# main.net
KiCad netlist of a schematic drawn in EAGLE
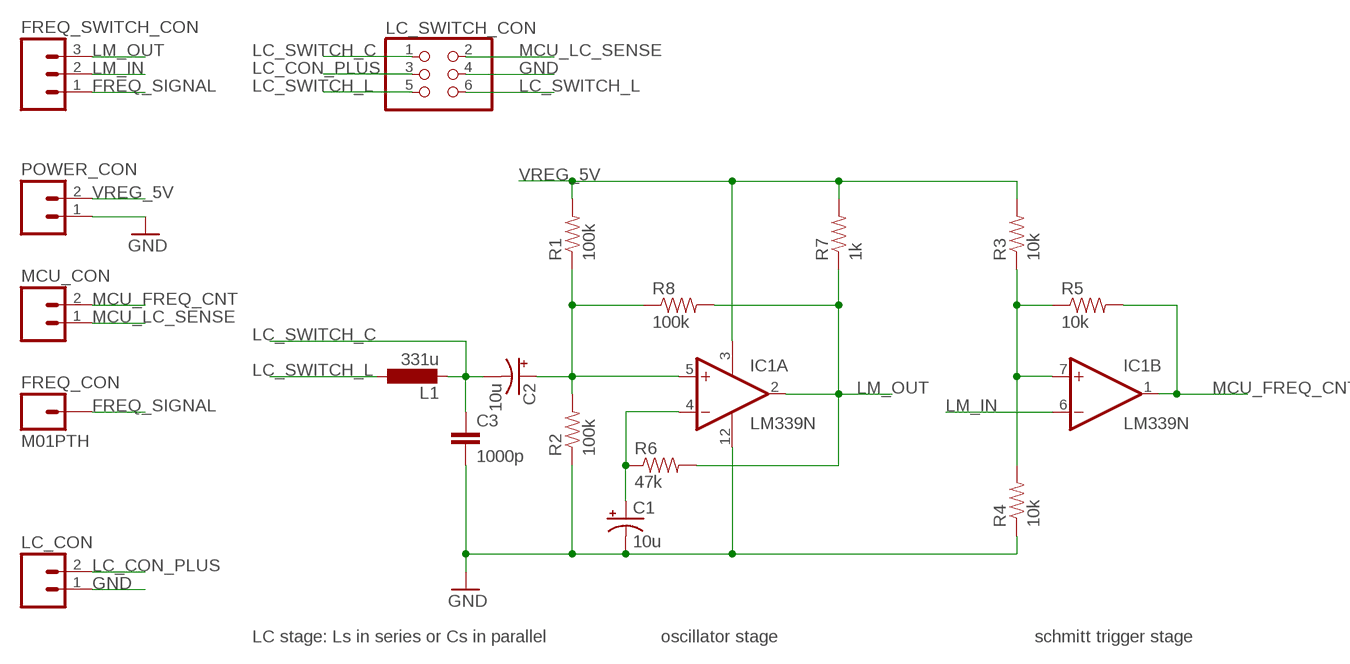
[diagram p0: schematic, sheet 1]

(export (version "E")
  (design (tool "Eeschema 10.0.6"))
  (components
    (comp (ref "C1")
      (value "10u")
      (footprint "eagle-import:CPOL-RADIAL-100UF-25V")
      (libsource (lib "eagle-import") (part "CAP_POLPTH1"))
    )
    (comp (ref "C2")
      (value "10u")
      (footprint "eagle-import:CPOL-RADIAL-100UF-25V")
      (libsource (lib "eagle-import") (part "CAP_POLPTH1"))
    )
    (comp (ref "C3")
      (value "1000p")
      (footprint "eagle-import:CAP-PTH-SMALL-KIT")
      (libsource (lib "eagle-import") (part "CAPKIT"))
    )
    (comp (ref "FREQ_CON")
      (value "M01PTH")
      (footprint "eagle-import:1X01")
      (libsource (lib "eagle-import") (part "M01PTH"))
    )
    (comp (ref "FREQ_SWITCH_CON")
      (value "M03PTH")
      (footprint "eagle-import:1X03")
      (libsource (lib "eagle-import") (part "M03PTH"))
    )
    (comp (ref "IC1")
      (value "LM339N")
      (footprint "eagle-import:DIL14")
      (libsource (lib "eagle-import") (part "LM339N"))
    )
    (comp (ref "L1")
      (value "331u")
      (footprint "eagle-import:0207_10")
      (libsource (lib "eagle-import") (part "L-EU0207/10"))
    )
    (comp (ref "LC_CON")
      (value "M02PTH")
      (footprint "eagle-import:1X02")
      (libsource (lib "eagle-import") (part "M02PTH"))
    )
    (comp (ref "LC_SWITCH_CON")
      (value "PINHD-2X3")
      (footprint "eagle-import:2X03")
      (libsource (lib "eagle-import") (part "PINHD-2X3"))
    )
    (comp (ref "MCU_CON")
      (value "M02PTH")
      (footprint "eagle-import:1X02")
      (libsource (lib "eagle-import") (part "M02PTH"))
    )
    (comp (ref "POWER_CON")
      (value "M02PTH")
      (footprint "eagle-import:1X02")
      (libsource (lib "eagle-import") (part "M02PTH"))
    )
    (comp (ref "R1")
      (value "100k")
      (footprint "eagle-import:AXIAL-0.4")
      (libsource (lib "eagle-import") (part "RESISTORPTH-1/4W"))
    )
    (comp (ref "R2")
      (value "100k")
      (footprint "eagle-import:AXIAL-0.4")
      (libsource (lib "eagle-import") (part "RESISTORPTH-1/4W"))
    )
    (comp (ref "R3")
      (value "10k")
      (footprint "eagle-import:AXIAL-0.4")
      (libsource (lib "eagle-import") (part "RESISTORPTH-1/4W"))
    )
    (comp (ref "R4")
      (value "10k")
      (footprint "eagle-import:AXIAL-0.4")
      (libsource (lib "eagle-import") (part "RESISTORPTH-1/4W"))
    )
    (comp (ref "R5")
      (value "10k")
      (footprint "eagle-import:AXIAL-0.4")
      (libsource (lib "eagle-import") (part "RESISTORPTH-1/4W"))
    )
    (comp (ref "R6")
      (value "47k")
      (footprint "eagle-import:AXIAL-0.4")
      (libsource (lib "eagle-import") (part "RESISTORPTH-1/4W"))
    )
    (comp (ref "R7")
      (value "1k")
      (footprint "eagle-import:AXIAL-0.4")
      (libsource (lib "eagle-import") (part "RESISTORPTH-1/4W"))
    )
    (comp (ref "R8")
      (value "100k")
      (footprint "eagle-import:AXIAL-0.4")
      (libsource (lib "eagle-import") (part "RESISTORPTH-1/4W"))
    )
  )
  (nets
    (net (code "1") (name "/FREQ_SIGNAL") (class "Default")
      (node (ref "FREQ_CON") (pin "1") (pinfunction "1_1") (pintype "passive"))
      (node (ref "FREQ_SWITCH_CON") (pin "1") (pinfunction "1_1") (pintype "passive"))
    )
    (net (code "2") (name "/LC_CON_PLUS") (class "Default")
      (node (ref "LC_CON") (pin "2") (pinfunction "2_2") (pintype "passive"))
      (node (ref "LC_SWITCH_CON") (pin "3") (pinfunction "3_3") (pintype "passive"))
    )
    (net (code "3") (name "/LC_SWITCH_C") (class "Default")
      (node (ref "C2") (pin "2") (pinfunction "-_2") (pintype "passive"))
      (node (ref "C3") (pin "1") (pinfunction "1_1") (pintype "passive"))
      (node (ref "L1") (pin "2") (pinfunction "2_2") (pintype "passive"))
      (node (ref "LC_SWITCH_CON") (pin "1") (pinfunction "1_1") (pintype "passive"))
    )
    (net (code "4") (name "/LC_SWITCH_L") (class "Default")
      (node (ref "L1") (pin "1") (pinfunction "1_1") (pintype "passive"))
      (node (ref "LC_SWITCH_CON") (pin "5") (pinfunction "5_5") (pintype "passive"))
      (node (ref "LC_SWITCH_CON") (pin "6") (pinfunction "6_6") (pintype "passive"))
    )
    (net (code "5") (name "/LM_IN") (class "Default")
      (node (ref "FREQ_SWITCH_CON") (pin "2") (pinfunction "2_2") (pintype "passive"))
      (node (ref "IC1") (pin "6") (pinfunction "-IN_6") (pintype "input"))
    )
    (net (code "6") (name "/LM_OUT") (class "Default")
      (node (ref "FREQ_SWITCH_CON") (pin "3") (pinfunction "3_3") (pintype "passive"))
      (node (ref "IC1") (pin "2") (pinfunction "OUT_2") (pintype "open_collector"))
      (node (ref "R6") (pin "P$2") (pinfunction "2_P$2") (pintype "passive"))
      (node (ref "R7") (pin "P$1") (pinfunction "1_P$1") (pintype "passive"))
      (node (ref "R8") (pin "P$2") (pinfunction "2_P$2") (pintype "passive"))
    )
    (net (code "7") (name "/MCU_FREQ_CNT") (class "Default")
      (node (ref "IC1") (pin "1") (pinfunction "OUT_1") (pintype "open_collector"))
      (node (ref "MCU_CON") (pin "2") (pinfunction "2_2") (pintype "passive"))
      (node (ref "R5") (pin "P$2") (pinfunction "2_P$2") (pintype "passive"))
    )
    (net (code "8") (name "/MCU_LC_SENSE") (class "Default")
      (node (ref "LC_SWITCH_CON") (pin "2") (pinfunction "2_2") (pintype "passive"))
      (node (ref "MCU_CON") (pin "1") (pinfunction "1_1") (pintype "passive"))
    )
    (net (code "9") (name "/VREG_5V") (class "Default")
      (node (ref "IC1") (pin "3") (pinfunction "V+_3") (pintype "power_in"))
      (node (ref "POWER_CON") (pin "2") (pinfunction "2_2") (pintype "passive"))
      (node (ref "R1") (pin "P$2") (pinfunction "2_P$2") (pintype "passive"))
      (node (ref "R3") (pin "P$2") (pinfunction "2_P$2") (pintype "passive"))
      (node (ref "R7") (pin "P$2") (pinfunction "2_P$2") (pintype "passive"))
    )
    (net (code "10") (name "GND") (class "Default")
      (node (ref "C1") (pin "2") (pinfunction "-_2") (pintype "passive"))
      (node (ref "C3") (pin "2") (pinfunction "2_2") (pintype "passive"))
      (node (ref "IC1") (pin "12") (pinfunction "GND_12") (pintype "power_in"))
      (node (ref "LC_CON") (pin "1") (pinfunction "1_1") (pintype "passive"))
      (node (ref "LC_SWITCH_CON") (pin "4") (pinfunction "4_4") (pintype "passive"))
      (node (ref "POWER_CON") (pin "1") (pinfunction "1_1") (pintype "passive"))
      (node (ref "R2") (pin "P$1") (pinfunction "1_P$1") (pintype "passive"))
      (node (ref "R4") (pin "P$1") (pinfunction "1_P$1") (pintype "passive"))
    )
    (net (code "11") (name "Net-(C1-+)") (class "Default")
      (node (ref "C1") (pin "1") (pinfunction "+_1") (pintype "passive"))
      (node (ref "IC1") (pin "4") (pinfunction "-IN_4") (pintype "input"))
      (node (ref "R6") (pin "P$1") (pinfunction "1_P$1") (pintype "passive"))
    )
    (net (code "12") (name "Net-(C2-+)") (class "Default")
      (node (ref "C2") (pin "1") (pinfunction "+_1") (pintype "passive"))
      (node (ref "IC1") (pin "5") (pinfunction "+IN_5") (pintype "input"))
      (node (ref "R1") (pin "P$1") (pinfunction "1_P$1") (pintype "passive"))
      (node (ref "R2") (pin "P$2") (pinfunction "2_P$2") (pintype "passive"))
      (node (ref "R8") (pin "P$1") (pinfunction "1_P$1") (pintype "passive"))
    )
    (net (code "13") (name "Net-(IC1B-+IN)") (class "Default")
      (node (ref "IC1") (pin "7") (pinfunction "+IN_7") (pintype "input"))
      (node (ref "R3") (pin "P$1") (pinfunction "1_P$1") (pintype "passive"))
      (node (ref "R4") (pin "P$2") (pinfunction "2_P$2") (pintype "passive"))
      (node (ref "R5") (pin "P$1") (pinfunction "1_P$1") (pintype "passive"))
    )
  )
)
